# isa.net
KiCad netlist of a schematic drawn in EAGLE
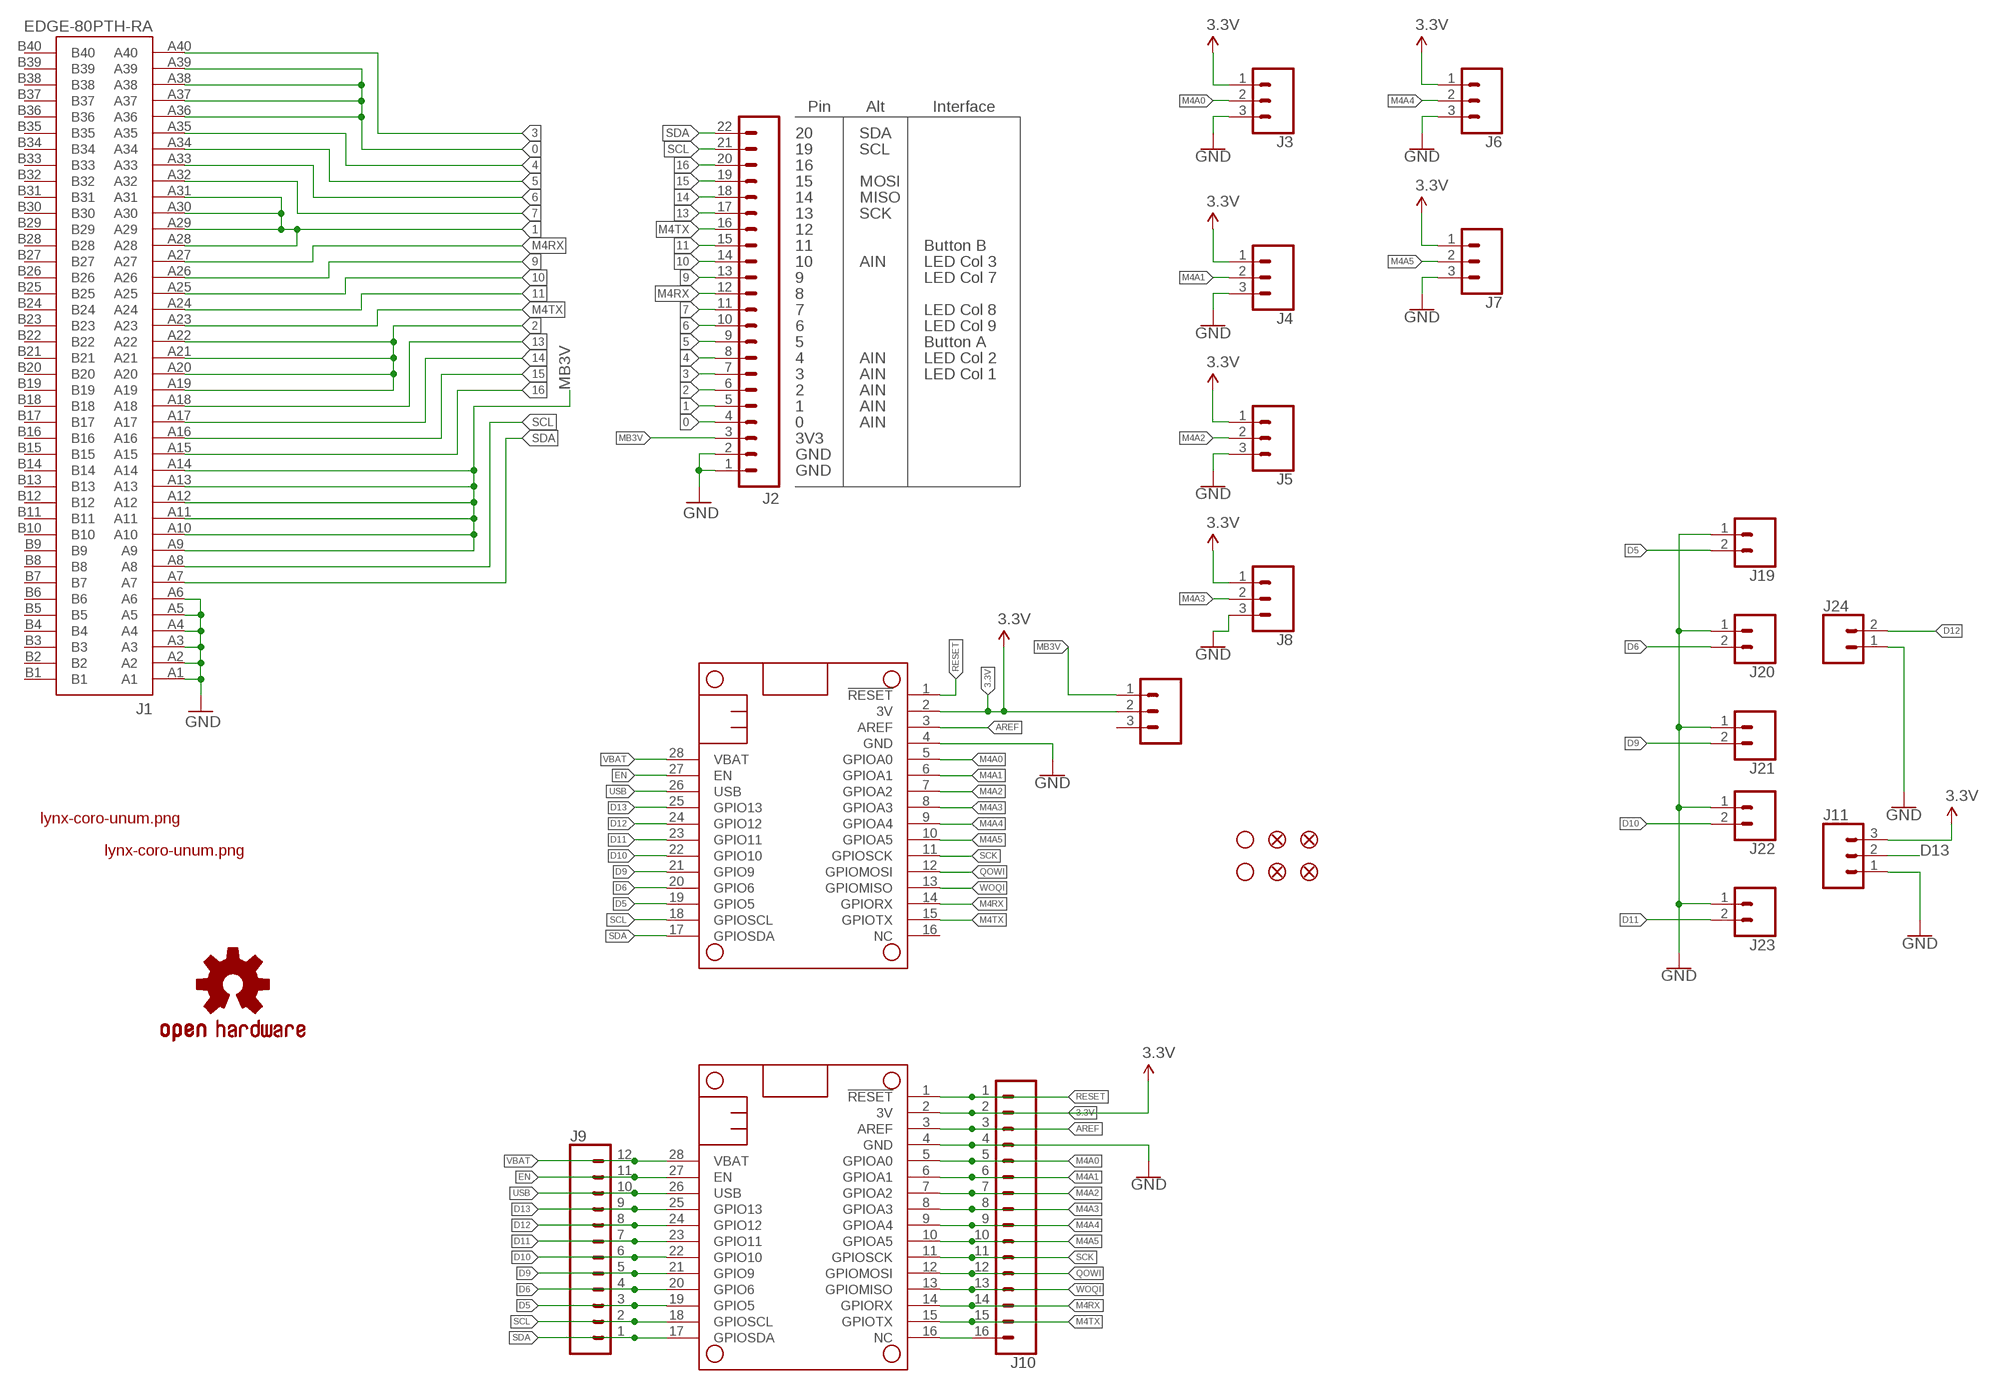
[diagram p0: schematic, sheet 1]

(export (version "E")
  (design (tool "Eeschema 10.0.6"))
  (components
    (comp (ref "FD1")
      (value "FIDUCIAL1X2")
      (footprint "eagle-import:FIDUCIAL-1X2")
      (libsource (lib "eagle-import") (part "FIDUCIAL1X2"))
    )
    (comp (ref "FD2")
      (value "FIDUCIAL1X2")
      (footprint "eagle-import:FIDUCIAL-1X2")
      (libsource (lib "eagle-import") (part "FIDUCIAL1X2"))
    )
    (comp (ref "FD3")
      (value "FIDUCIAL1X2")
      (footprint "eagle-import:FIDUCIAL-1X2")
      (libsource (lib "eagle-import") (part "FIDUCIAL1X2"))
    )
    (comp (ref "FD4")
      (value "FIDUCIAL1X2")
      (footprint "eagle-import:FIDUCIAL-1X2")
      (libsource (lib "eagle-import") (part "FIDUCIAL1X2"))
    )
    (comp (ref "H1")
      (value "STAND-OFF")
      (footprint "eagle-import:STAND-OFF")
      (libsource (lib "eagle-import") (part "STAND-OFF"))
    )
    (comp (ref "H2")
      (value "STAND-OFF")
      (footprint "eagle-import:STAND-OFF")
      (libsource (lib "eagle-import") (part "STAND-OFF"))
    )
    (comp (ref "J1")
      (value "EDGE-80PTH-RA")
      (footprint "eagle-import:VEC-127-080-R")
      (libsource (lib "eagle-import") (part "EDGE-80PTH-RA"))
    )
    (comp (ref "J2")
      (value "M22PTH")
      (footprint "eagle-import:1X22")
      (libsource (lib "eagle-import") (part "M22PTH"))
    )
    (comp (ref "J3")
      (value "CONN_03SCREW")
      (footprint "eagle-import:SCREWTERMINAL-3.5MM-3")
      (libsource (lib "eagle-import") (part "CONN_03SCREW"))
    )
    (comp (ref "J4")
      (value "CONN_03SCREW")
      (footprint "eagle-import:SCREWTERMINAL-3.5MM-3")
      (libsource (lib "eagle-import") (part "CONN_03SCREW"))
    )
    (comp (ref "J5")
      (value "CONN_03SCREW")
      (footprint "eagle-import:SCREWTERMINAL-3.5MM-3")
      (libsource (lib "eagle-import") (part "CONN_03SCREW"))
    )
    (comp (ref "J6")
      (value "CONN_03SCREW")
      (footprint "eagle-import:SCREWTERMINAL-3.5MM-3")
      (libsource (lib "eagle-import") (part "CONN_03SCREW"))
    )
    (comp (ref "J7")
      (value "CONN_03SCREW")
      (footprint "eagle-import:SCREWTERMINAL-3.5MM-3")
      (libsource (lib "eagle-import") (part "CONN_03SCREW"))
    )
    (comp (ref "J8")
      (value "CONN_03SCREW")
      (footprint "eagle-import:SCREWTERMINAL-3.5MM-3")
      (libsource (lib "eagle-import") (part "CONN_03SCREW"))
    )
    (comp (ref "J9")
      (value "CONN_12LOCK")
      (footprint "eagle-import:1X12_LOCK")
      (libsource (lib "eagle-import") (part "CONN_12LOCK"))
    )
    (comp (ref "J10")
      (value "CONN_16LOCK")
      (footprint "eagle-import:1X16_LOCK")
      (libsource (lib "eagle-import") (part "CONN_16LOCK"))
    )
    (comp (ref "J11")
      (value "CONN_03SCREW")
      (footprint "eagle-import:SCREWTERMINAL-3.5MM-3")
      (libsource (lib "eagle-import") (part "CONN_03SCREW"))
    )
    (comp (ref "J12")
      (value "CONN_03")
      (footprint "eagle-import:1X03")
      (libsource (lib "eagle-import") (part "CONN_03"))
    )
    (comp (ref "J19")
      (value "CONN_023.5MM")
      (footprint "eagle-import:SCREWTERMINAL-3.5MM-2")
      (libsource (lib "eagle-import") (part "CONN_023.5MM"))
    )
    (comp (ref "J20")
      (value "CONN_023.5MM")
      (footprint "eagle-import:SCREWTERMINAL-3.5MM-2")
      (libsource (lib "eagle-import") (part "CONN_023.5MM"))
    )
    (comp (ref "J21")
      (value "CONN_023.5MM")
      (footprint "eagle-import:SCREWTERMINAL-3.5MM-2")
      (libsource (lib "eagle-import") (part "CONN_023.5MM"))
    )
    (comp (ref "J22")
      (value "CONN_023.5MM")
      (footprint "eagle-import:SCREWTERMINAL-3.5MM-2")
      (libsource (lib "eagle-import") (part "CONN_023.5MM"))
    )
    (comp (ref "J23")
      (value "CONN_023.5MM")
      (footprint "eagle-import:SCREWTERMINAL-3.5MM-2")
      (libsource (lib "eagle-import") (part "CONN_023.5MM"))
    )
    (comp (ref "J24")
      (value "CONN_023.5MM")
      (footprint "eagle-import:SCREWTERMINAL-3.5MM-2")
      (libsource (lib "eagle-import") (part "CONN_023.5MM"))
    )
    (comp (ref "LOGO3")
      (value "OSHW-LOGOS")
      (footprint "eagle-import:OSHW-LOGO-S")
      (libsource (lib "eagle-import") (part "OSHW-LOGOS"))
    )
    (comp (ref "MS1")
      (value "FEATHERWING_NODIM")
      (footprint "eagle-import:FEATHERWING_DIM")
      (libsource (lib "eagle-import") (part "FEATHERWING_NODIM"))
    )
    (comp (ref "MS2")
      (value "FEATHERWING_NODIM")
      (footprint "eagle-import:FEATHERWING_DIM")
      (libsource (lib "eagle-import") (part "FEATHERWING_NODIM"))
    )
    (comp (ref "U$3")
      (value "LYNX#CORO#UNUM#PNG")
      (footprint "eagle-import:LYNX#CORO#UNUM#PNG")
      (libsource (lib "eagle-import") (part "lynx#coro#unum#png_LYNX#CORO#UNUM#PNG"))
    )
    (comp (ref "U$4")
      (value "LYNX#CORO#UNUM#PNG")
      (footprint "eagle-import:LYNX#CORO#UNUM#PNG")
      (libsource (lib "eagle-import") (part "LYNX#CORO#UNUM#PNG"))
    )
  )
  (nets
    (net (code "1") (name "0") (class "Default")
      (node (ref "J1") (pin "A36") (pinfunction "A36_A36") (pintype "bidirectional"))
      (node (ref "J1") (pin "A37") (pinfunction "A37_A37") (pintype "bidirectional"))
      (node (ref "J1") (pin "A38") (pinfunction "A38_A38") (pintype "bidirectional"))
      (node (ref "J1") (pin "A39") (pinfunction "A39_A39") (pintype "bidirectional"))
      (node (ref "J2") (pin "4") (pinfunction "4_4") (pintype "passive"))
    )
    (net (code "2") (name "1") (class "Default")
      (node (ref "J1") (pin "A28") (pinfunction "A28_A28") (pintype "bidirectional"))
      (node (ref "J1") (pin "A29") (pinfunction "A29_A29") (pintype "bidirectional"))
      (node (ref "J1") (pin "A30") (pinfunction "A30_A30") (pintype "bidirectional"))
      (node (ref "J1") (pin "A31") (pinfunction "A31_A31") (pintype "bidirectional"))
      (node (ref "J2") (pin "5") (pinfunction "5_5") (pintype "passive"))
    )
    (net (code "3") (name "2") (class "Default")
      (node (ref "J1") (pin "A19") (pinfunction "A19_A19") (pintype "bidirectional"))
      (node (ref "J1") (pin "A20") (pinfunction "A20_A20") (pintype "bidirectional"))
      (node (ref "J1") (pin "A21") (pinfunction "A21_A21") (pintype "bidirectional"))
      (node (ref "J1") (pin "A22") (pinfunction "A22_A22") (pintype "bidirectional"))
      (node (ref "J2") (pin "6") (pinfunction "6_6") (pintype "passive"))
    )
    (net (code "4") (name "3") (class "Default")
      (node (ref "J1") (pin "A40") (pinfunction "A40_A40") (pintype "bidirectional"))
      (node (ref "J2") (pin "7") (pinfunction "7_7") (pintype "passive"))
    )
    (net (code "5") (name "3.3V") (class "Default")
      (node (ref "J10") (pin "2") (pinfunction "2_2") (pintype "passive"))
      (node (ref "J11") (pin "3") (pinfunction "3_3") (pintype "passive"))
      (node (ref "J12") (pin "2") (pinfunction "2_2") (pintype "passive"))
      (node (ref "J3") (pin "1") (pinfunction "1_1") (pintype "passive"))
      (node (ref "J4") (pin "1") (pinfunction "1_1") (pintype "passive"))
      (node (ref "J5") (pin "1") (pinfunction "1_1") (pintype "passive"))
      (node (ref "J6") (pin "1") (pinfunction "1_1") (pintype "passive"))
      (node (ref "J7") (pin "1") (pinfunction "1_1") (pintype "passive"))
      (node (ref "J8") (pin "1") (pinfunction "1_1") (pintype "passive"))
      (node (ref "MS1") (pin "2") (pinfunction "3V_2") (pintype "power_in"))
      (node (ref "MS2") (pin "2") (pinfunction "3V_2") (pintype "power_in"))
    )
    (net (code "6") (name "4") (class "Default")
      (node (ref "J1") (pin "A35") (pinfunction "A35_A35") (pintype "bidirectional"))
      (node (ref "J2") (pin "8") (pinfunction "8_8") (pintype "passive"))
    )
    (net (code "7") (name "5") (class "Default")
      (node (ref "J1") (pin "A34") (pinfunction "A34_A34") (pintype "bidirectional"))
      (node (ref "J2") (pin "9") (pinfunction "9_9") (pintype "passive"))
    )
    (net (code "8") (name "6") (class "Default")
      (node (ref "J1") (pin "A33") (pinfunction "A33_A33") (pintype "bidirectional"))
      (node (ref "J2") (pin "10") (pinfunction "10_10") (pintype "passive"))
    )
    (net (code "9") (name "7") (class "Default")
      (node (ref "J1") (pin "A32") (pinfunction "A32_A32") (pintype "bidirectional"))
      (node (ref "J2") (pin "11") (pinfunction "11_11") (pintype "passive"))
    )
    (net (code "10") (name "9") (class "Default")
      (node (ref "J1") (pin "A26") (pinfunction "A26_A26") (pintype "bidirectional"))
      (node (ref "J2") (pin "13") (pinfunction "13_13") (pintype "passive"))
    )
    (net (code "11") (name "10") (class "Default")
      (node (ref "J1") (pin "A25") (pinfunction "A25_A25") (pintype "bidirectional"))
      (node (ref "J2") (pin "14") (pinfunction "14_14") (pintype "passive"))
    )
    (net (code "12") (name "11") (class "Default")
      (node (ref "J1") (pin "A24") (pinfunction "A24_A24") (pintype "bidirectional"))
      (node (ref "J2") (pin "15") (pinfunction "15_15") (pintype "passive"))
    )
    (net (code "13") (name "13") (class "Default")
      (node (ref "J1") (pin "A18") (pinfunction "A18_A18") (pintype "bidirectional"))
      (node (ref "J2") (pin "17") (pinfunction "17_17") (pintype "passive"))
    )
    (net (code "14") (name "14") (class "Default")
      (node (ref "J1") (pin "A17") (pinfunction "A17_A17") (pintype "bidirectional"))
      (node (ref "J2") (pin "18") (pinfunction "18_18") (pintype "passive"))
    )
    (net (code "15") (name "15") (class "Default")
      (node (ref "J1") (pin "A16") (pinfunction "A16_A16") (pintype "bidirectional"))
      (node (ref "J2") (pin "19") (pinfunction "19_19") (pintype "passive"))
    )
    (net (code "16") (name "16") (class "Default")
      (node (ref "J1") (pin "A15") (pinfunction "A15_A15") (pintype "bidirectional"))
      (node (ref "J2") (pin "20") (pinfunction "20_20") (pintype "passive"))
    )
    (net (code "17") (name "AREF") (class "Default")
      (node (ref "J10") (pin "3") (pinfunction "3_3") (pintype "passive"))
      (node (ref "MS1") (pin "3") (pinfunction "AREF_3") (pintype "passive"))
      (node (ref "MS2") (pin "3") (pinfunction "AREF_3") (pintype "passive"))
    )
    (net (code "18") (name "D5") (class "Default")
      (node (ref "J19") (pin "2") (pinfunction "2_2") (pintype "passive"))
      (node (ref "J9") (pin "3") (pinfunction "3_3") (pintype "passive"))
      (node (ref "MS1") (pin "19") (pinfunction "GPIO5_19") (pintype "bidirectional"))
      (node (ref "MS2") (pin "19") (pinfunction "GPIO5_19") (pintype "bidirectional"))
    )
    (net (code "19") (name "D6") (class "Default")
      (node (ref "J20") (pin "2") (pinfunction "2_2") (pintype "passive"))
      (node (ref "J9") (pin "4") (pinfunction "4_4") (pintype "passive"))
      (node (ref "MS1") (pin "20") (pinfunction "GPIO6_20") (pintype "bidirectional"))
      (node (ref "MS2") (pin "20") (pinfunction "GPIO6_20") (pintype "bidirectional"))
    )
    (net (code "20") (name "D9") (class "Default")
      (node (ref "J21") (pin "2") (pinfunction "2_2") (pintype "passive"))
      (node (ref "J9") (pin "5") (pinfunction "5_5") (pintype "passive"))
      (node (ref "MS1") (pin "21") (pinfunction "GPIO9_21") (pintype "bidirectional"))
      (node (ref "MS2") (pin "21") (pinfunction "GPIO9_21") (pintype "bidirectional"))
    )
    (net (code "21") (name "D10") (class "Default")
      (node (ref "J22") (pin "2") (pinfunction "2_2") (pintype "passive"))
      (node (ref "J9") (pin "6") (pinfunction "6_6") (pintype "passive"))
      (node (ref "MS1") (pin "22") (pinfunction "GPIO10_22") (pintype "bidirectional"))
      (node (ref "MS2") (pin "22") (pinfunction "GPIO10_22") (pintype "bidirectional"))
    )
    (net (code "22") (name "D11") (class "Default")
      (node (ref "J23") (pin "2") (pinfunction "2_2") (pintype "passive"))
      (node (ref "J9") (pin "7") (pinfunction "7_7") (pintype "passive"))
      (node (ref "MS1") (pin "23") (pinfunction "GPIO11_23") (pintype "bidirectional"))
      (node (ref "MS2") (pin "23") (pinfunction "GPIO11_23") (pintype "bidirectional"))
    )
    (net (code "23") (name "D12") (class "Default")
      (node (ref "J24") (pin "2") (pinfunction "2_2") (pintype "passive"))
      (node (ref "J9") (pin "8") (pinfunction "8_8") (pintype "passive"))
      (node (ref "MS1") (pin "24") (pinfunction "GPIO12_24") (pintype "bidirectional"))
      (node (ref "MS2") (pin "24") (pinfunction "GPIO12_24") (pintype "bidirectional"))
    )
    (net (code "24") (name "D13") (class "Default")
      (node (ref "J11") (pin "2") (pinfunction "2_2") (pintype "passive"))
      (node (ref "J9") (pin "9") (pinfunction "9_9") (pintype "passive"))
      (node (ref "MS1") (pin "25") (pinfunction "GPIO13_25") (pintype "bidirectional"))
      (node (ref "MS2") (pin "25") (pinfunction "GPIO13_25") (pintype "bidirectional"))
    )
    (net (code "25") (name "EN") (class "Default")
      (node (ref "J9") (pin "11") (pinfunction "11_11") (pintype "passive"))
      (node (ref "MS1") (pin "27") (pinfunction "EN_27") (pintype "passive"))
      (node (ref "MS2") (pin "27") (pinfunction "EN_27") (pintype "passive"))
    )
    (net (code "26") (name "GND") (class "Default")
      (node (ref "J1") (pin "A1") (pinfunction "A1_A1") (pintype "bidirectional"))
      (node (ref "J1") (pin "A2") (pinfunction "A2_A2") (pintype "bidirectional"))
      (node (ref "J1") (pin "A3") (pinfunction "A3_A3") (pintype "bidirectional"))
      (node (ref "J1") (pin "A4") (pinfunction "A4_A4") (pintype "bidirectional"))
      (node (ref "J1") (pin "A5") (pinfunction "A5_A5") (pintype "bidirectional"))
      (node (ref "J1") (pin "A6") (pinfunction "A6_A6") (pintype "bidirectional"))
      (node (ref "J10") (pin "4") (pinfunction "4_4") (pintype "passive"))
      (node (ref "J11") (pin "1") (pinfunction "1_1") (pintype "passive"))
      (node (ref "J19") (pin "1") (pinfunction "1_1") (pintype "passive"))
      (node (ref "J2") (pin "1") (pinfunction "1_1") (pintype "passive"))
      (node (ref "J2") (pin "2") (pinfunction "2_2") (pintype "passive"))
      (node (ref "J20") (pin "1") (pinfunction "1_1") (pintype "passive"))
      (node (ref "J21") (pin "1") (pinfunction "1_1") (pintype "passive"))
      (node (ref "J22") (pin "1") (pinfunction "1_1") (pintype "passive"))
      (node (ref "J23") (pin "1") (pinfunction "1_1") (pintype "passive"))
      (node (ref "J24") (pin "1") (pinfunction "1_1") (pintype "passive"))
      (node (ref "J3") (pin "3") (pinfunction "3_3") (pintype "passive"))
      (node (ref "J4") (pin "3") (pinfunction "3_3") (pintype "passive"))
      (node (ref "J5") (pin "3") (pinfunction "3_3") (pintype "passive"))
      (node (ref "J6") (pin "3") (pinfunction "3_3") (pintype "passive"))
      (node (ref "J7") (pin "3") (pinfunction "3_3") (pintype "passive"))
      (node (ref "J8") (pin "3") (pinfunction "3_3") (pintype "passive"))
      (node (ref "MS1") (pin "4") (pinfunction "GND_4") (pintype "power_in"))
      (node (ref "MS2") (pin "4") (pinfunction "GND_4") (pintype "power_in"))
    )
    (net (code "27") (name "M4A0") (class "Default")
      (node (ref "J10") (pin "5") (pinfunction "5_5") (pintype "passive"))
      (node (ref "J3") (pin "2") (pinfunction "2_2") (pintype "passive"))
      (node (ref "MS1") (pin "5") (pinfunction "GPIOA0_5") (pintype "bidirectional"))
      (node (ref "MS2") (pin "5") (pinfunction "GPIOA0_5") (pintype "bidirectional"))
    )
    (net (code "28") (name "M4A1") (class "Default")
      (node (ref "J10") (pin "6") (pinfunction "6_6") (pintype "passive"))
      (node (ref "J4") (pin "2") (pinfunction "2_2") (pintype "passive"))
      (node (ref "MS1") (pin "6") (pinfunction "GPIOA1_6") (pintype "bidirectional"))
      (node (ref "MS2") (pin "6") (pinfunction "GPIOA1_6") (pintype "bidirectional"))
    )
    (net (code "29") (name "M4A2") (class "Default")
      (node (ref "J10") (pin "7") (pinfunction "7_7") (pintype "passive"))
      (node (ref "J5") (pin "2") (pinfunction "2_2") (pintype "passive"))
      (node (ref "MS1") (pin "7") (pinfunction "GPIOA2_7") (pintype "bidirectional"))
      (node (ref "MS2") (pin "7") (pinfunction "GPIOA2_7") (pintype "bidirectional"))
    )
    (net (code "30") (name "M4A3") (class "Default")
      (node (ref "J10") (pin "8") (pinfunction "8_8") (pintype "passive"))
      (node (ref "J8") (pin "2") (pinfunction "2_2") (pintype "passive"))
      (node (ref "MS1") (pin "8") (pinfunction "GPIOA3_8") (pintype "bidirectional"))
      (node (ref "MS2") (pin "8") (pinfunction "GPIOA3_8") (pintype "bidirectional"))
    )
    (net (code "31") (name "M4A4") (class "Default")
      (node (ref "J10") (pin "9") (pinfunction "9_9") (pintype "passive"))
      (node (ref "J6") (pin "2") (pinfunction "2_2") (pintype "passive"))
      (node (ref "MS1") (pin "9") (pinfunction "GPIOA4_9") (pintype "bidirectional"))
      (node (ref "MS2") (pin "9") (pinfunction "GPIOA4_9") (pintype "bidirectional"))
    )
    (net (code "32") (name "M4A5") (class "Default")
      (node (ref "J10") (pin "10") (pinfunction "10_10") (pintype "passive"))
      (node (ref "J7") (pin "2") (pinfunction "2_2") (pintype "passive"))
      (node (ref "MS1") (pin "10") (pinfunction "GPIOA5_10") (pintype "bidirectional"))
      (node (ref "MS2") (pin "10") (pinfunction "GPIOA5_10") (pintype "bidirectional"))
    )
    (net (code "33") (name "M4RX") (class "Default")
      (node (ref "J1") (pin "A27") (pinfunction "A27_A27") (pintype "bidirectional"))
      (node (ref "J10") (pin "14") (pinfunction "14_14") (pintype "passive"))
      (node (ref "J2") (pin "12") (pinfunction "12_12") (pintype "passive"))
      (node (ref "MS1") (pin "14") (pinfunction "GPIORX_14") (pintype "bidirectional"))
      (node (ref "MS2") (pin "14") (pinfunction "GPIORX_14") (pintype "bidirectional"))
    )
    (net (code "34") (name "M4TX") (class "Default")
      (node (ref "J1") (pin "A23") (pinfunction "A23_A23") (pintype "bidirectional"))
      (node (ref "J10") (pin "15") (pinfunction "15_15") (pintype "passive"))
      (node (ref "J2") (pin "16") (pinfunction "16_16") (pintype "passive"))
      (node (ref "MS1") (pin "15") (pinfunction "GPIOTX_15") (pintype "bidirectional"))
      (node (ref "MS2") (pin "15") (pinfunction "GPIOTX_15") (pintype "bidirectional"))
    )
    (net (code "35") (name "MB3V") (class "Default")
      (node (ref "J1") (pin "A10") (pinfunction "A10_A10") (pintype "bidirectional"))
      (node (ref "J1") (pin "A11") (pinfunction "A11_A11") (pintype "bidirectional"))
      (node (ref "J1") (pin "A12") (pinfunction "A12_A12") (pintype "bidirectional"))
      (node (ref "J1") (pin "A13") (pinfunction "A13_A13") (pintype "bidirectional"))
      (node (ref "J1") (pin "A14") (pinfunction "A14_A14") (pintype "bidirectional"))
      (node (ref "J1") (pin "A9") (pinfunction "A9_A9") (pintype "bidirectional"))
      (node (ref "J12") (pin "1") (pinfunction "1_1") (pintype "passive"))
      (node (ref "J2") (pin "3") (pinfunction "3_3") (pintype "passive"))
    )
    (net (code "36") (name "Net-(MS2-NC)") (class "Default")
      (node (ref "J10") (pin "16") (pinfunction "16_16") (pintype "passive"))
      (node (ref "MS2") (pin "16") (pinfunction "NC_16") (pintype "passive"))
    )
    (net (code "37") (name "QOWI") (class "Default")
      (node (ref "J10") (pin "12") (pinfunction "12_12") (pintype "passive"))
      (node (ref "MS1") (pin "12") (pinfunction "GPIOMOSI_12") (pintype "bidirectional"))
      (node (ref "MS2") (pin "12") (pinfunction "GPIOMOSI_12") (pintype "bidirectional"))
    )
    (net (code "38") (name "RESET") (class "Default")
      (node (ref "J10") (pin "1") (pinfunction "1_1") (pintype "passive"))
      (node (ref "MS1") (pin "1") (pinfunction "~{RESET}_1") (pintype "input"))
      (node (ref "MS2") (pin "1") (pinfunction "~{RESET}_1") (pintype "input"))
    )
    (net (code "39") (name "SCK") (class "Default")
      (node (ref "J10") (pin "11") (pinfunction "11_11") (pintype "passive"))
      (node (ref "MS1") (pin "11") (pinfunction "GPIOSCK_11") (pintype "bidirectional"))
      (node (ref "MS2") (pin "11") (pinfunction "GPIOSCK_11") (pintype "bidirectional"))
    )
    (net (code "40") (name "SCL") (class "Default")
      (node (ref "J1") (pin "A8") (pinfunction "A8_A8") (pintype "bidirectional"))
      (node (ref "J2") (pin "21") (pinfunction "21_21") (pintype "passive"))
      (node (ref "J9") (pin "2") (pinfunction "2_2") (pintype "passive"))
      (node (ref "MS1") (pin "18") (pinfunction "GPIOSCL_18") (pintype "bidirectional"))
      (node (ref "MS2") (pin "18") (pinfunction "GPIOSCL_18") (pintype "bidirectional"))
    )
    (net (code "41") (name "SDA") (class "Default")
      (node (ref "J1") (pin "A7") (pinfunction "A7_A7") (pintype "bidirectional"))
      (node (ref "J2") (pin "22") (pinfunction "22_22") (pintype "passive"))
      (node (ref "J9") (pin "1") (pinfunction "1_1") (pintype "passive"))
      (node (ref "MS1") (pin "17") (pinfunction "GPIOSDA_17") (pintype "bidirectional"))
      (node (ref "MS2") (pin "17") (pinfunction "GPIOSDA_17") (pintype "bidirectional"))
    )
    (net (code "42") (name "USB") (class "Default")
      (node (ref "J9") (pin "10") (pinfunction "10_10") (pintype "passive"))
      (node (ref "MS1") (pin "26") (pinfunction "USB_26") (pintype "power_in"))
      (node (ref "MS2") (pin "26") (pinfunction "USB_26") (pintype "power_in"))
    )
    (net (code "43") (name "VBAT") (class "Default")
      (node (ref "J9") (pin "12") (pinfunction "12_12") (pintype "passive"))
      (node (ref "MS1") (pin "28") (pinfunction "VBAT_28") (pintype "power_in"))
      (node (ref "MS2") (pin "28") (pinfunction "VBAT_28") (pintype "power_in"))
    )
    (net (code "44") (name "WOQI") (class "Default")
      (node (ref "J10") (pin "13") (pinfunction "13_13") (pintype "passive"))
      (node (ref "MS1") (pin "13") (pinfunction "GPIOMISO_13") (pintype "bidirectional"))
      (node (ref "MS2") (pin "13") (pinfunction "GPIOMISO_13") (pintype "bidirectional"))
    )
    (net (code "45") (name "unconnected-(J1-PadB1)") (class "Default")
      (node (ref "J1") (pin "B1") (pinfunction "B1_B1") (pintype "bidirectional"))
    )
    (net (code "46") (name "unconnected-(J1-PadB2)") (class "Default")
      (node (ref "J1") (pin "B2") (pinfunction "B2_B2") (pintype "bidirectional"))
    )
    (net (code "47") (name "unconnected-(J1-PadB3)") (class "Default")
      (node (ref "J1") (pin "B3") (pinfunction "B3_B3") (pintype "bidirectional"))
    )
    (net (code "48") (name "unconnected-(J1-PadB4)") (class "Default")
      (node (ref "J1") (pin "B4") (pinfunction "B4_B4") (pintype "bidirectional"))
    )
    (net (code "49") (name "unconnected-(J1-PadB5)") (class "Default")
      (node (ref "J1") (pin "B5") (pinfunction "B5_B5") (pintype "bidirectional"))
    )
    (net (code "50") (name "unconnected-(J1-PadB6)") (class "Default")
      (node (ref "J1") (pin "B6") (pinfunction "B6_B6") (pintype "bidirectional"))
    )
    (net (code "51") (name "unconnected-(J1-PadB7)") (class "Default")
      (node (ref "J1") (pin "B7") (pinfunction "B7_B7") (pintype "bidirectional"))
    )
    (net (code "52") (name "unconnected-(J1-PadB8)") (class "Default")
      (node (ref "J1") (pin "B8") (pinfunction "B8_B8") (pintype "bidirectional"))
    )
    (net (code "53") (name "unconnected-(J1-PadB9)") (class "Default")
      (node (ref "J1") (pin "B9") (pinfunction "B9_B9") (pintype "bidirectional"))
    )
    (net (code "54") (name "unconnected-(J1-PadB10)") (class "Default")
      (node (ref "J1") (pin "B10") (pinfunction "B10_B10") (pintype "bidirectional"))
    )
    (net (code "55") (name "unconnected-(J1-PadB11)") (class "Default")
      (node (ref "J1") (pin "B11") (pinfunction "B11_B11") (pintype "bidirectional"))
    )
    (net (code "56") (name "unconnected-(J1-PadB12)") (class "Default")
      (node (ref "J1") (pin "B12") (pinfunction "B12_B12") (pintype "bidirectional"))
    )
    (net (code "57") (name "unconnected-(J1-PadB13)") (class "Default")
      (node (ref "J1") (pin "B13") (pinfunction "B13_B13") (pintype "bidirectional"))
    )
    (net (code "58") (name "unconnected-(J1-PadB14)") (class "Default")
      (node (ref "J1") (pin "B14") (pinfunction "B14_B14") (pintype "bidirectional"))
    )
    (net (code "59") (name "unconnected-(J1-PadB15)") (class "Default")
      (node (ref "J1") (pin "B15") (pinfunction "B15_B15") (pintype "bidirectional"))
    )
    (net (code "60") (name "unconnected-(J1-PadB16)") (class "Default")
      (node (ref "J1") (pin "B16") (pinfunction "B16_B16") (pintype "bidirectional"))
    )
    (net (code "61") (name "unconnected-(J1-PadB17)") (class "Default")
      (node (ref "J1") (pin "B17") (pinfunction "B17_B17") (pintype "bidirectional"))
    )
    (net (code "62") (name "unconnected-(J1-PadB18)") (class "Default")
      (node (ref "J1") (pin "B18") (pinfunction "B18_B18") (pintype "bidirectional"))
    )
    (net (code "63") (name "unconnected-(J1-PadB19)") (class "Default")
      (node (ref "J1") (pin "B19") (pinfunction "B19_B19") (pintype "bidirectional"))
    )
    (net (code "64") (name "unconnected-(J1-PadB20)") (class "Default")
      (node (ref "J1") (pin "B20") (pinfunction "B20_B20") (pintype "bidirectional"))
    )
    (net (code "65") (name "unconnected-(J1-PadB21)") (class "Default")
      (node (ref "J1") (pin "B21") (pinfunction "B21_B21") (pintype "bidirectional"))
    )
    (net (code "66") (name "unconnected-(J1-PadB22)") (class "Default")
      (node (ref "J1") (pin "B22") (pinfunction "B22_B22") (pintype "bidirectional"))
    )
    (net (code "67") (name "unconnected-(J1-PadB23)") (class "Default")
      (node (ref "J1") (pin "B23") (pinfunction "B23_B23") (pintype "bidirectional"))
    )
    (net (code "68") (name "unconnected-(J1-PadB24)") (class "Default")
      (node (ref "J1") (pin "B24") (pinfunction "B24_B24") (pintype "bidirectional"))
    )
    (net (code "69") (name "unconnected-(J1-PadB25)") (class "Default")
      (node (ref "J1") (pin "B25") (pinfunction "B25_B25") (pintype "bidirectional"))
    )
    (net (code "70") (name "unconnected-(J1-PadB26)") (class "Default")
      (node (ref "J1") (pin "B26") (pinfunction "B26_B26") (pintype "bidirectional"))
    )
    (net (code "71") (name "unconnected-(J1-PadB27)") (class "Default")
      (node (ref "J1") (pin "B27") (pinfunction "B27_B27") (pintype "bidirectional"))
    )
    (net (code "72") (name "unconnected-(J1-PadB28)") (class "Default")
      (node (ref "J1") (pin "B28") (pinfunction "B28_B28") (pintype "bidirectional"))
    )
    (net (code "73") (name "unconnected-(J1-PadB29)") (class "Default")
      (node (ref "J1") (pin "B29") (pinfunction "B29_B29") (pintype "bidirectional"))
    )
    (net (code "74") (name "unconnected-(J1-PadB30)") (class "Default")
      (node (ref "J1") (pin "B30") (pinfunction "B30_B30") (pintype "bidirectional"))
    )
    (net (code "75") (name "unconnected-(J1-PadB31)") (class "Default")
      (node (ref "J1") (pin "B31") (pinfunction "B31_B31") (pintype "bidirectional"))
    )
    (net (code "76") (name "unconnected-(J1-PadB32)") (class "Default")
      (node (ref "J1") (pin "B32") (pinfunction "B32_B32") (pintype "bidirectional"))
    )
    (net (code "77") (name "unconnected-(J1-PadB33)") (class "Default")
      (node (ref "J1") (pin "B33") (pinfunction "B33_B33") (pintype "bidirectional"))
    )
    (net (code "78") (name "unconnected-(J1-PadB34)") (class "Default")
      (node (ref "J1") (pin "B34") (pinfunction "B34_B34") (pintype "bidirectional"))
    )
    (net (code "79") (name "unconnected-(J1-PadB35)") (class "Default")
      (node (ref "J1") (pin "B35") (pinfunction "B35_B35") (pintype "bidirectional"))
    )
    (net (code "80") (name "unconnected-(J1-PadB36)") (class "Default")
      (node (ref "J1") (pin "B36") (pinfunction "B36_B36") (pintype "bidirectional"))
    )
    (net (code "81") (name "unconnected-(J1-PadB37)") (class "Default")
      (node (ref "J1") (pin "B37") (pinfunction "B37_B37") (pintype "bidirectional"))
    )
    (net (code "82") (name "unconnected-(J1-PadB38)") (class "Default")
      (node (ref "J1") (pin "B38") (pinfunction "B38_B38") (pintype "bidirectional"))
    )
    (net (code "83") (name "unconnected-(J1-PadB39)") (class "Default")
      (node (ref "J1") (pin "B39") (pinfunction "B39_B39") (pintype "bidirectional"))
    )
    (net (code "84") (name "unconnected-(J1-PadB40)") (class "Default")
      (node (ref "J1") (pin "B40") (pinfunction "B40_B40") (pintype "bidirectional"))
    )
    (net (code "85") (name "unconnected-(J12-Pad3)") (class "Default")
      (node (ref "J12") (pin "3") (pinfunction "3_3") (pintype "passive"))
    )
    (net (code "86") (name "unconnected-(MS1-NC-Pad16)") (class "Default")
      (node (ref "MS1") (pin "16") (pinfunction "NC_16") (pintype "passive"))
    )
  )
)
